# 3_cyber60-1_mcu.net
KiCad netlist of a schematic drawn in Altium Designer
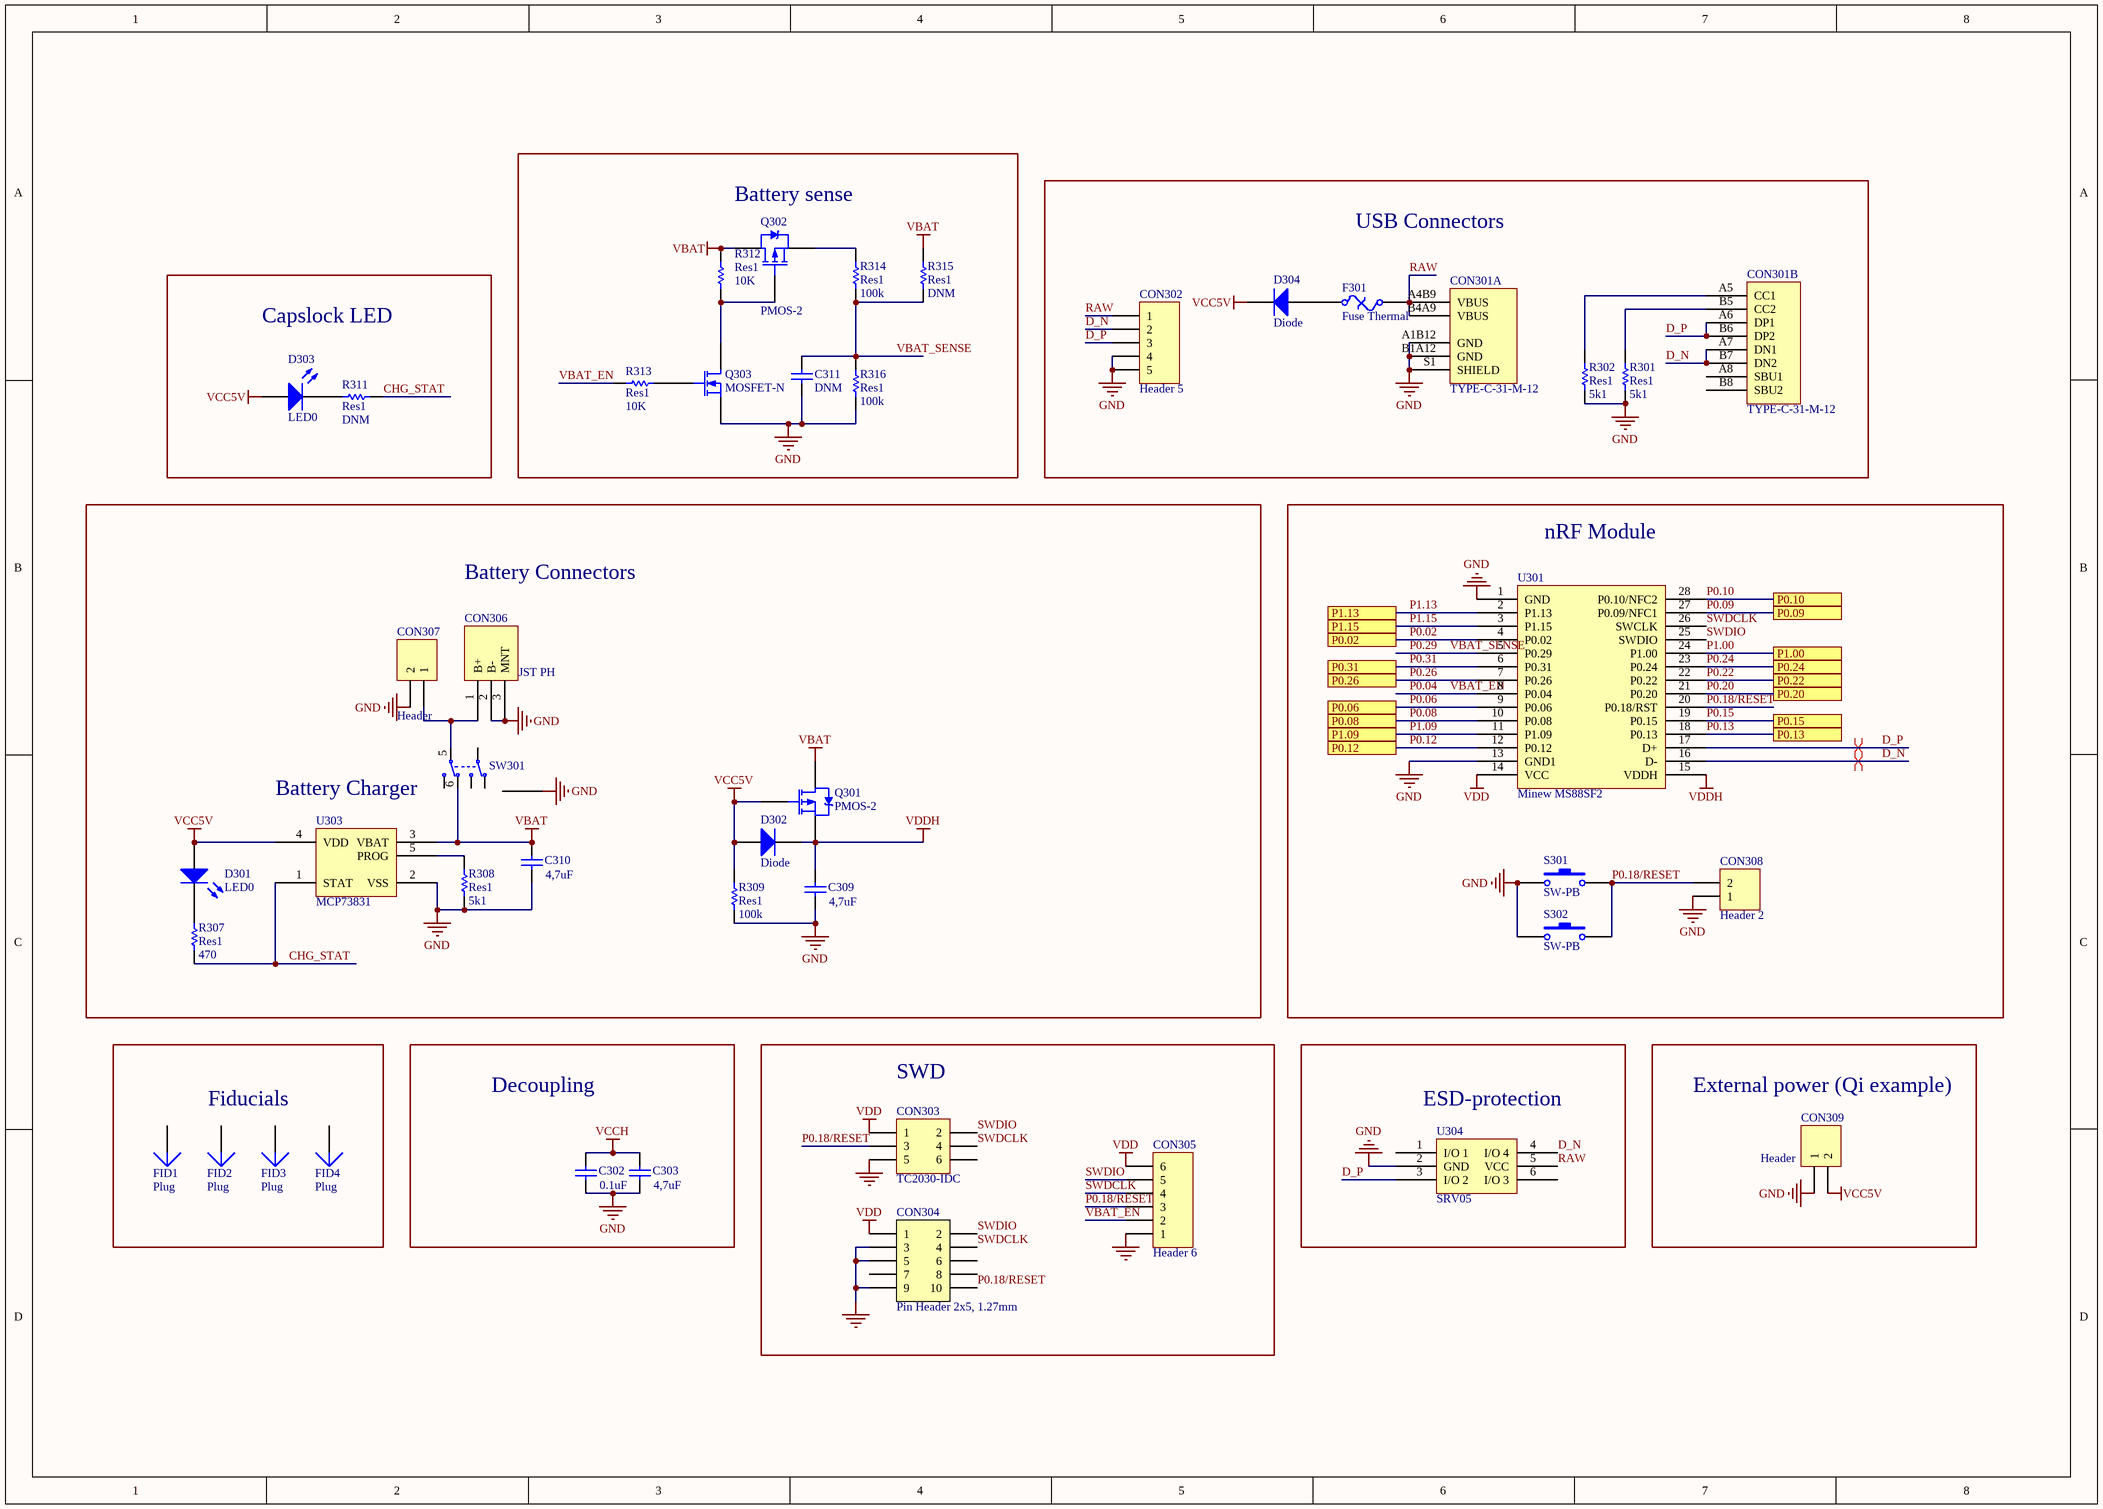
[diagram p0: 3_cyber60-1_mcu.SchDoc]

(export (version "E")
  (design (tool "Eeschema 10.0.6"))
  (components
    (comp (ref "C302")
      (value "0.1uF")
      (footprint "C0603[1608]")
      (description "Capacitor")
      (fields (field (name "MFG") "KEMET") (field (name "LCSC PART #") "C14663"))
      (libsource (lib "Miscellaneous Devices") (part "Cap"))
    )
    (comp (ref "C303")
      (value "4,7uF")
      (footprint "C0603[1608]")
      (description "Capacitor")
      (fields (field (name "LCSC PART #") "C19666") (field (name "MRF.PART") "CL10A475KO8NNNC"))
      (libsource (lib "Miscellaneous Devices") (part "Cap"))
    )
    (comp (ref "C309")
      (value "4,7uF")
      (footprint "C0603[1608]")
      (description "Capacitor")
      (fields (field (name "LCSC PART #") "C19666") (field (name "MRF.PART") "CL10A475KO8NNNC"))
      (libsource (lib "Miscellaneous Devices") (part "Cap"))
    )
    (comp (ref "C310")
      (value "4,7uF")
      (footprint "C0603[1608]")
      (description "Capacitor")
      (fields (field (name "LCSC PART #") "C19666") (field (name "MRF.PART") "CL10A475KO8NNNC"))
      (libsource (lib "Miscellaneous Devices") (part "Cap"))
    )
    (comp (ref "C311")
      (value "DNM")
      (footprint "C0603[1608]")
      (description "Capacitor")
      (libsource (lib "Miscellaneous Devices") (part "Cap"))
    )
    (comp (ref "CON301")
      (value "TYPE-C-31-M-12")
      (footprint "TYPE-C-31-M-12")
      (fields (field (name "MFG") "Korean Hroparts Elec"))
      (libsource (lib "Keebs") (part "TYPE-C-31-M-12"))
    )
    (comp (ref "CON302")
      (value "Header 5")
      (footprint "JST SM04B-SRSS-TB")
      (description "Header, 5-Pin")
      (fields (field (name "MFG") "JST Sales America Inc.") (field (name "MRF.PART") "SM04B-SRSS-TB(LF)(SN)"))
      (libsource (lib "Miscellaneous Connectors") (part "Header 5"))
    )
    (comp (ref "CON303")
      (value "TC2030-IDC")
      (footprint "TC2030-IDC-NL")
      (description "Header, 3-Pin, Dual row")
      (libsource (lib "Miscellaneous Connectors") (part "Header 3X2"))
    )
    (comp (ref "CON304")
      (value "Pin Header 2x5, 1.27mm")
      (footprint "HDR_2x5-SMD-1.27mm-K")
      (description "Pin Header 2x5, 1.27mm (50mil), SMD, Keying Shroud")
      (fields (field (name "MFG") "Samtec Inc."))
      (libsource (lib "Nordic Passive DB") (part "CONN-2x5"))
    )
    (comp (ref "CON305")
      (value "Header 6")
      (footprint "HDR1X6")
      (description "Header, 6-Pin")
      (fields (field (name "PUBLISHER") "Altium Limited"))
      (libsource (lib "Miscellaneous Connectors") (part "Header 6"))
    )
    (comp (ref "CON306")
      (value "JST PH")
      (footprint "JST SM02B-SRSS-TB")
      (fields (field (name "LCSC PART #") "C160402") (field (name "MRF.PART") "SM02B-SRSS-TB(LF)(SN)"))
      (libsource (lib "Keebs") (part "JST S2B-PH-SM4-TB"))
    )
    (comp (ref "CON307")
      (value "Header")
      (footprint "Keebs:JST S2B-PH-K(LF)(SN)")
      (description "Header, 2-Pin")
      (fields (field (name "LCSC PART #") "C265016") (field (name "MRF.PART") "S2B-PH-K(LF)(SN)"))
      (libsource (lib "") (part "Header 2_1"))
    )
    (comp (ref "CON308")
      (value "Header 2")
      (footprint "HDR1X2")
      (description "Header, 2-Pin")
      (libsource (lib "Miscellaneous Connectors") (part "Header 2"))
    )
    (comp (ref "CON309")
      (value "Header")
      (footprint "HDR1X2")
      (description "Header, 2-Pin")
      (libsource (lib "Miscellaneous Connectors") (part "Header 2"))
    )
    (comp (ref "D301")
      (value "LED0")
      (footprint "LED0603[1608]")
      (description "Typical INFRARED GaAs LED")
      (fields (field (name "LCSC PART #") "C72038") (field (name "MRF.PART") "19-213/Y2C-CQ2R2L/3T(CY)"))
      (libsource (lib "Miscellaneous Devices") (part "LED0"))
    )
    (comp (ref "D302")
      (value "Diode")
      (footprint "SOD-123")
      (description "Default Diode")
      (fields (field (name "LCSC PART #") "C8598") (field (name "MRF.PART") "B5819W"))
      (libsource (lib "Miscellaneous Devices") (part "Diode"))
    )
    (comp (ref "D303")
      (value "LED0")
      (footprint "MX-switch - CAPS - LED NO SWITCH")
      (description "Typical INFRARED GaAs LED")
      (fields (field (name "MFG") "Kingbright"))
      (libsource (lib "Miscellaneous Devices") (part "LED0"))
    )
    (comp (ref "D304")
      (value "Diode")
      (footprint "SOD-123")
      (description "Default Diode")
      (fields (field (name "LCSC PART #") "C8598") (field (name "MRF.PART") "B5819W"))
      (libsource (lib "Miscellaneous Devices") (part "Diode"))
    )
    (comp (ref "F301")
      (value "Fuse Thermal")
      (footprint "C1206[3216]")
      (description "Thermal Fuse")
      (fields (field (name "MFG") "Bel Fuse Inc.") (field (name "LCSC PART #") "C135338"))
      (libsource (lib "Miscellaneous Devices") (part "Fuse Thermal"))
    )
    (comp (ref "FID1")
      (value "Plug")
      (footprint "Fiducial_Nordic")
      (libsource (lib "Miscellaneous Connectors") (part "Plug"))
    )
    (comp (ref "FID2")
      (value "Plug")
      (footprint "Fiducial_Nordic")
      (libsource (lib "Miscellaneous Connectors") (part "Plug"))
    )
    (comp (ref "FID3")
      (value "Plug")
      (footprint "Fiducial_Nordic")
      (libsource (lib "Miscellaneous Connectors") (part "Plug"))
    )
    (comp (ref "FID4")
      (value "Plug")
      (footprint "Fiducial_Nordic")
      (libsource (lib "Miscellaneous Connectors") (part "Plug"))
    )
    (comp (ref "Q301")
      (value "PMOS-2")
      (footprint "SOT-23-3")
      (description "P-Channel Power MOSFET")
      (fields (field (name "MRF.PART") "SI2301CDS-T1-GE3") (field (name "LCSC PART #") "C10487"))
      (libsource (lib "Miscellaneous Devices") (part "PMOS-2"))
    )
    (comp (ref "Q302")
      (value "PMOS-2")
      (footprint "SOT-23-3")
      (description "P-Channel Power MOSFET")
      (fields (field (name "MRF.PART") "SI2301CDS-T1-GE3") (field (name "LCSC PART #") "C10487"))
      (libsource (lib "Miscellaneous Devices") (part "PMOS-2"))
    )
    (comp (ref "Q303")
      (value "MOSFET-N")
      (footprint "SOT-23-3")
      (description "N-Channel MOSFET")
      (fields (field (name "LCSC PART #") "C8545") (field (name "MRF.PART") "2N7002"))
      (libsource (lib "Miscellaneous Devices") (part "MOSFET-N"))
    )
    (comp (ref "R301")
      (value "Res1")
      (footprint "R0603[1608]")
      (description "Resistor")
      (fields
        (field (name "ALTIUM_VALUE") "5k1")
        (field (name "MFG") "Panasonic Electronic Components")
        (field (name "LCSC PART #") "C23186")
      )
      (libsource (lib "Miscellaneous Devices") (part "Res1"))
    )
    (comp (ref "R302")
      (value "Res1")
      (footprint "R0603[1608]")
      (description "Resistor")
      (fields
        (field (name "ALTIUM_VALUE") "5k1")
        (field (name "MFG") "Panasonic Electronic Components")
        (field (name "LCSC PART #") "C23186")
      )
      (libsource (lib "Miscellaneous Devices") (part "Res1"))
    )
    (comp (ref "R307")
      (value "Res1")
      (footprint "R0603[1608]")
      (description "Resistor")
      (fields
        (field (name "ALTIUM_VALUE") "470")
        (field (name "MFG") "Panasonic Electronic Components")
        (field (name "LCSC PART #") "C23179")
      )
      (libsource (lib "Miscellaneous Devices") (part "Res1"))
    )
    (comp (ref "R308")
      (value "Res1")
      (footprint "R0603[1608]")
      (description "Resistor")
      (fields
        (field (name "ALTIUM_VALUE") "5k1")
        (field (name "MFG") "Panasonic Electronic Components")
        (field (name "LCSC PART #") "C23186")
      )
      (libsource (lib "Miscellaneous Devices") (part "Res1"))
    )
    (comp (ref "R309")
      (value "Res1")
      (footprint "R0603[1608]")
      (description "Resistor")
      (fields
        (field (name "ALTIUM_VALUE") "100k")
        (field (name "MRF.PART") "0603WAF1003T5E")
        (field (name "LCSC PART #") "C25803")
      )
      (libsource (lib "Miscellaneous Devices") (part "Res1"))
    )
    (comp (ref "R311")
      (value "Res1")
      (footprint "R0603[1608]")
      (description "Resistor")
      (fields (field (name "ALTIUM_VALUE") "DNM"))
      (libsource (lib "Miscellaneous Devices") (part "Res1"))
    )
    (comp (ref "R312")
      (value "Res1")
      (footprint "R0603[1608]")
      (description "Resistor")
      (fields
        (field (name "ALTIUM_VALUE") "10K")
        (field (name "MFG") "Panasonic Electronic Components")
        (field (name "LCSC PART #") "C25804")
      )
      (libsource (lib "Miscellaneous Devices") (part "Res1"))
    )
    (comp (ref "R313")
      (value "Res1")
      (footprint "R0603[1608]")
      (description "Resistor")
      (fields
        (field (name "ALTIUM_VALUE") "10K")
        (field (name "MFG") "Panasonic Electronic Components")
        (field (name "LCSC PART #") "C25804")
      )
      (libsource (lib "Miscellaneous Devices") (part "Res1"))
    )
    (comp (ref "R314")
      (value "Res1")
      (footprint "R0603[1608]")
      (description "Resistor")
      (fields
        (field (name "ALTIUM_VALUE") "100k")
        (field (name "MRF.PART") "0603WAF1003T5E")
        (field (name "LCSC PART #") "C25803")
      )
      (libsource (lib "Miscellaneous Devices") (part "Res1"))
    )
    (comp (ref "R315")
      (value "Res1")
      (footprint "R0603[1608]")
      (description "Resistor")
      (fields (field (name "ALTIUM_VALUE") "DNM") (field (name "MFG") "TE Connectivity Passive Product"))
      (libsource (lib "Miscellaneous Devices") (part "Res1"))
    )
    (comp (ref "R316")
      (value "Res1")
      (footprint "R0603[1608]")
      (description "Resistor")
      (fields
        (field (name "ALTIUM_VALUE") "100k")
        (field (name "MRF.PART") "0603WAF1003T5E")
        (field (name "LCSC PART #") "C25803")
      )
      (libsource (lib "Miscellaneous Devices") (part "Res1"))
    )
    (comp (ref "S301")
      (value "SW-PB")
      (footprint "Combo switch")
      (description "Switch")
      (fields (field (name "MFG") "C&K") (field (name "MRF.PART") "TS-1187A-C-D-B"))
      (libsource (lib "Miscellaneous Devices") (part "SW-PB"))
    )
    (comp (ref "S302")
      (value "SW-PB")
      (footprint "Combo switch")
      (description "Switch")
      (fields (field (name "MFG") "C&K") (field (name "MRF.PART") "TS-1187A-C-D-B"))
      (libsource (lib "Miscellaneous Devices") (part "SW-PB"))
    )
    (comp (ref "SW301")
      (value "~")
      (footprint "AlpsAlpine SSSS820201")
      (description "Slide Switch DPDT")
      (fields (field (name "MRF.PART") "SSSS820201") (field (name "LCSC PART #") "C160879"))
      (libsource (lib "Keebs") (part "MKH-22D14-G2-B"))
    )
    (comp (ref "U301")
      (value "Minew MS88SF2")
      (footprint "Minew MS88SF2")
      (fields (field (name "MFG") "Minew"))
      (libsource (lib "Keebs") (part "Minew MS88SF2"))
    )
    (comp (ref "U303")
      (value "MCP73831")
      (footprint "SOT-23-5")
      (fields (field (name "LCSC PART #") "C32574") (field (name "MRF.PART") "TP4054"))
      (libsource (lib "Keebs") (part "MCP73831"))
    )
    (comp (ref "U304")
      (value "SRV05")
      (footprint "SOT-23-6")
      (fields (field (name "LCSC PART #") "C85364") (field (name "MRF.PART") "SRV05-4-P-T7"))
      (libsource (lib "Keebs") (part "SRV05"))
    )
  )
  (nets
    (net (code "1") (name "/CHG_STAT") (class "Default")
      (node (ref "R307") (pin "1") (pinfunction "1_1") (pintype "passive"))
      (node (ref "R311") (pin "1") (pinfunction "1_1") (pintype "passive"))
      (node (ref "U303") (pin "1") (pinfunction "STAT_1") (pintype "passive"))
    )
    (net (code "2") (name "/D_N") (class "Default")
      (node (ref "CON301") (pin "A7") (pinfunction "DN1_A7") (pintype "passive"))
      (node (ref "CON301") (pin "B7") (pinfunction "DN2_B7") (pintype "passive"))
      (node (ref "CON302") (pin "2") (pinfunction "2_2") (pintype "passive"))
      (node (ref "U301") (pin "16") (pinfunction "D-_16") (pintype "passive"))
      (node (ref "U304") (pin "4") (pinfunction "I/O_4_4") (pintype "passive"))
    )
    (net (code "3") (name "/D_P") (class "Default")
      (node (ref "CON301") (pin "A6") (pinfunction "DP1_A6") (pintype "passive"))
      (node (ref "CON301") (pin "B6") (pinfunction "DP2_B6") (pintype "passive"))
      (node (ref "CON302") (pin "3") (pinfunction "3_3") (pintype "passive"))
      (node (ref "U301") (pin "17") (pinfunction "D+_17") (pintype "passive"))
      (node (ref "U304") (pin "3") (pinfunction "I/O_2_3") (pintype "passive"))
    )
    (net (code "4") (name "/P0.02") (class "Default")
      (node (ref "U301") (pin "4") (pinfunction "P0.02_4") (pintype "passive"))
    )
    (net (code "5") (name "/P0.04") (class "Default")
      (node (ref "CON305") (pin "2") (pinfunction "2_2") (pintype "passive"))
      (node (ref "R313") (pin "1") (pinfunction "1_1") (pintype "passive"))
      (node (ref "U301") (pin "8") (pinfunction "P0.04_8") (pintype "passive"))
    )
    (net (code "6") (name "/P0.06") (class "Default")
      (node (ref "U301") (pin "9") (pinfunction "P0.06_9") (pintype "passive"))
    )
    (net (code "7") (name "/P0.08") (class "Default")
      (node (ref "U301") (pin "10") (pinfunction "P0.08_10") (pintype "passive"))
    )
    (net (code "8") (name "/P0.09") (class "Default")
      (node (ref "U301") (pin "27") (pinfunction "P0.09/NFC1_27") (pintype "passive"))
    )
    (net (code "9") (name "/P0.10") (class "Default")
      (node (ref "U301") (pin "28") (pinfunction "P0.10/NFC2_28") (pintype "passive"))
    )
    (net (code "10") (name "/P0.12") (class "Default")
      (node (ref "U301") (pin "12") (pinfunction "P0.12_12") (pintype "passive"))
    )
    (net (code "11") (name "/P0.13") (class "Default")
      (node (ref "U301") (pin "18") (pinfunction "P0.13_18") (pintype "passive"))
    )
    (net (code "12") (name "/P0.15") (class "Default")
      (node (ref "U301") (pin "19") (pinfunction "P0.15_19") (pintype "passive"))
    )
    (net (code "13") (name "/P0.18{slash}RESET") (class "Default")
      (node (ref "CON303") (pin "3") (pinfunction "3_3") (pintype "passive"))
      (node (ref "CON304") (pin "10") (pinfunction "10_10") (pintype "passive"))
      (node (ref "CON305") (pin "3") (pinfunction "3_3") (pintype "passive"))
      (node (ref "CON308") (pin "2") (pinfunction "2_2") (pintype "passive"))
      (node (ref "S301") (pin "2") (pinfunction "2_2") (pintype "passive"))
      (node (ref "S302") (pin "1") (pinfunction "1_1") (pintype "passive"))
      (node (ref "U301") (pin "20") (pinfunction "P0.18/RST_20") (pintype "passive"))
    )
    (net (code "14") (name "/P0.20") (class "Default")
      (node (ref "U301") (pin "21") (pinfunction "P0.20_21") (pintype "passive"))
    )
    (net (code "15") (name "/P0.22") (class "Default")
      (node (ref "U301") (pin "22") (pinfunction "P0.22_22") (pintype "passive"))
    )
    (net (code "16") (name "/P0.24") (class "Default")
      (node (ref "U301") (pin "23") (pinfunction "P0.24_23") (pintype "passive"))
    )
    (net (code "17") (name "/P0.26") (class "Default")
      (node (ref "U301") (pin "7") (pinfunction "P0.26_7") (pintype "passive"))
    )
    (net (code "18") (name "/P0.29") (class "Default")
      (node (ref "C311") (pin "2") (pinfunction "2_2") (pintype "passive"))
      (node (ref "R314") (pin "2") (pinfunction "2_2") (pintype "passive"))
      (node (ref "R315") (pin "1") (pinfunction "1_1") (pintype "passive"))
      (node (ref "R316") (pin "1") (pinfunction "1_1") (pintype "passive"))
      (node (ref "U301") (pin "5") (pinfunction "P0.29_5") (pintype "passive"))
    )
    (net (code "19") (name "/P0.31") (class "Default")
      (node (ref "U301") (pin "6") (pinfunction "P0.31_6") (pintype "passive"))
    )
    (net (code "20") (name "/P1.00") (class "Default")
      (node (ref "U301") (pin "24") (pinfunction "P1.00_24") (pintype "passive"))
    )
    (net (code "21") (name "/P1.09") (class "Default")
      (node (ref "U301") (pin "11") (pinfunction "P1.09_11") (pintype "passive"))
    )
    (net (code "22") (name "/P1.13") (class "Default")
      (node (ref "U301") (pin "2") (pinfunction "P1.13_2") (pintype "passive"))
    )
    (net (code "23") (name "/P1.15") (class "Default")
      (node (ref "U301") (pin "3") (pinfunction "P1.15_3") (pintype "passive"))
    )
    (net (code "24") (name "/RAW") (class "Default")
      (node (ref "CON301") (pin "A4B9") (pinfunction "VBUS_A4B9") (pintype "passive"))
      (node (ref "CON301") (pin "B4A9") (pinfunction "VBUS_B4A9") (pintype "passive"))
      (node (ref "CON302") (pin "1") (pinfunction "1_1") (pintype "passive"))
      (node (ref "F301") (pin "2") (pinfunction "2_2") (pintype "passive"))
      (node (ref "U304") (pin "5") (pinfunction "VCC_5") (pintype "passive"))
    )
    (net (code "25") (name "/SWDCLK") (class "Default")
      (node (ref "CON303") (pin "4") (pinfunction "4_4") (pintype "passive"))
      (node (ref "CON304") (pin "4") (pinfunction "4_4") (pintype "passive"))
      (node (ref "CON305") (pin "4") (pinfunction "4_4") (pintype "passive"))
      (node (ref "U301") (pin "26") (pinfunction "SWCLK_26") (pintype "passive"))
    )
    (net (code "26") (name "/SWDIO") (class "Default")
      (node (ref "CON303") (pin "2") (pinfunction "2_2") (pintype "passive"))
      (node (ref "CON304") (pin "2") (pinfunction "2_2") (pintype "passive"))
      (node (ref "CON305") (pin "5") (pinfunction "5_5") (pintype "passive"))
      (node (ref "U301") (pin "25") (pinfunction "SWDIO_25") (pintype "passive"))
    )
    (net (code "27") (name "GND") (class "Default")
      (node (ref "C302") (pin "1") (pinfunction "1_1") (pintype "passive"))
      (node (ref "C303") (pin "1") (pinfunction "1_1") (pintype "passive"))
      (node (ref "C309") (pin "1") (pinfunction "1_1") (pintype "passive"))
      (node (ref "C310") (pin "1") (pinfunction "1_1") (pintype "passive"))
      (node (ref "C311") (pin "1") (pinfunction "1_1") (pintype "passive"))
      (node (ref "CON301") (pin "A1B12") (pinfunction "GND_A1B12") (pintype "passive"))
      (node (ref "CON301") (pin "B1A12") (pinfunction "GND_B1A12") (pintype "passive"))
      (node (ref "CON301") (pin "S1") (pinfunction "SHIELD_S1") (pintype "passive"))
      (node (ref "CON302") (pin "4") (pinfunction "4_4") (pintype "passive"))
      (node (ref "CON302") (pin "5") (pinfunction "5_5") (pintype "passive"))
      (node (ref "CON303") (pin "5") (pinfunction "5_5") (pintype "passive"))
      (node (ref "CON304") (pin "3") (pinfunction "3_3") (pintype "passive"))
      (node (ref "CON304") (pin "5") (pinfunction "5_5") (pintype "passive"))
      (node (ref "CON304") (pin "9") (pinfunction "9_9") (pintype "passive"))
      (node (ref "CON305") (pin "1") (pinfunction "1_1") (pintype "passive"))
      (node (ref "CON306") (pin "2") (pinfunction "B-_2") (pintype "passive"))
      (node (ref "CON306") (pin "3") (pinfunction "MNT_3") (pintype "passive"))
      (node (ref "CON307") (pin "2") (pinfunction "2_2") (pintype "passive"))
      (node (ref "CON308") (pin "1") (pinfunction "1_1") (pintype "passive"))
      (node (ref "CON309") (pin "1") (pinfunction "1_1") (pintype "passive"))
      (node (ref "Q303") (pin "2") (pinfunction "S_2") (pintype "passive"))
      (node (ref "R301") (pin "2") (pinfunction "2_2") (pintype "passive"))
      (node (ref "R302") (pin "2") (pinfunction "2_2") (pintype "passive"))
      (node (ref "R308") (pin "2") (pinfunction "2_2") (pintype "passive"))
      (node (ref "R309") (pin "2") (pinfunction "2_2") (pintype "passive"))
      (node (ref "R316") (pin "2") (pinfunction "2_2") (pintype "passive"))
      (node (ref "S301") (pin "1") (pinfunction "1_1") (pintype "passive"))
      (node (ref "S302") (pin "2") (pinfunction "2_2") (pintype "passive"))
      (node (ref "SW301") (pin "7") (pinfunction "MNT_7") (pintype "passive"))
      (node (ref "U301") (pin "1") (pinfunction "GND_1") (pintype "passive"))
      (node (ref "U301") (pin "13") (pinfunction "GND1_13") (pintype "passive"))
      (node (ref "U303") (pin "2") (pinfunction "VSS_2") (pintype "passive"))
      (node (ref "U304") (pin "2") (pinfunction "GND_2") (pintype "passive"))
    )
    (net (code "28") (name "Net-(CON301B-CC1)") (class "Default")
      (node (ref "CON301") (pin "A5") (pinfunction "CC1_A5") (pintype "passive"))
      (node (ref "R302") (pin "1") (pinfunction "1_1") (pintype "passive"))
    )
    (net (code "29") (name "Net-(CON301B-CC2)") (class "Default")
      (node (ref "CON301") (pin "B5") (pinfunction "CC2_B5") (pintype "passive"))
      (node (ref "R301") (pin "1") (pinfunction "1_1") (pintype "passive"))
    )
    (net (code "30") (name "Net-(CON306-B+)") (class "Default")
      (node (ref "CON306") (pin "1") (pinfunction "B+_1") (pintype "passive"))
      (node (ref "CON307") (pin "1") (pinfunction "1_1") (pintype "passive"))
      (node (ref "SW301") (pin "5") (pinfunction "COM-2_5") (pintype "passive"))
    )
    (net (code "31") (name "Net-(D301-K)") (class "Default")
      (node (ref "D301") (pin "2") (pinfunction "K_2") (pintype "passive"))
      (node (ref "R307") (pin "2") (pinfunction "2_2") (pintype "passive"))
    )
    (net (code "32") (name "Net-(D303-K)") (class "Default")
      (node (ref "D303") (pin "2") (pinfunction "K_2") (pintype "passive"))
      (node (ref "R311") (pin "2") (pinfunction "2_2") (pintype "passive"))
    )
    (net (code "33") (name "Net-(D304-A)") (class "Default")
      (node (ref "D304") (pin "1") (pinfunction "A_1") (pintype "passive"))
      (node (ref "F301") (pin "1") (pinfunction "1_1") (pintype "passive"))
    )
    (net (code "34") (name "Net-(Q302-G)") (class "Default")
      (node (ref "Q302") (pin "1") (pinfunction "G_1") (pintype "passive"))
      (node (ref "Q303") (pin "3") (pinfunction "D_3") (pintype "passive"))
      (node (ref "R312") (pin "2") (pinfunction "2_2") (pintype "passive"))
    )
    (net (code "35") (name "Net-(Q302-S)") (class "Default")
      (node (ref "Q302") (pin "2") (pinfunction "S_2") (pintype "passive"))
      (node (ref "R314") (pin "1") (pinfunction "1_1") (pintype "passive"))
    )
    (net (code "36") (name "Net-(Q303-G)") (class "Default")
      (node (ref "Q303") (pin "1") (pinfunction "G_1") (pintype "passive"))
      (node (ref "R313") (pin "2") (pinfunction "2_2") (pintype "passive"))
    )
    (net (code "37") (name "Net-(U303-PROG)") (class "Default")
      (node (ref "R308") (pin "1") (pinfunction "1_1") (pintype "passive"))
      (node (ref "U303") (pin "5") (pinfunction "PROG_5") (pintype "passive"))
    )
    (net (code "38") (name "VBAT") (class "Default")
      (node (ref "C310") (pin "2") (pinfunction "2_2") (pintype "passive"))
      (node (ref "Q301") (pin "3") (pinfunction "D_3") (pintype "passive"))
      (node (ref "Q302") (pin "3") (pinfunction "D_3") (pintype "passive"))
      (node (ref "R312") (pin "1") (pinfunction "1_1") (pintype "passive"))
      (node (ref "R315") (pin "2") (pinfunction "2_2") (pintype "passive"))
      (node (ref "SW301") (pin "6") (pinfunction "N.C-2_6") (pintype "passive"))
      (node (ref "U303") (pin "3") (pinfunction "VBAT_3") (pintype "passive"))
    )
    (net (code "39") (name "VCC5V") (class "Default")
      (node (ref "CON309") (pin "2") (pinfunction "2_2") (pintype "passive"))
      (node (ref "D301") (pin "1") (pinfunction "A_1") (pintype "passive"))
      (node (ref "D302") (pin "1") (pinfunction "A_1") (pintype "passive"))
      (node (ref "D303") (pin "1") (pinfunction "A_1") (pintype "passive"))
      (node (ref "D304") (pin "2") (pinfunction "K_2") (pintype "passive"))
      (node (ref "Q301") (pin "1") (pinfunction "G_1") (pintype "passive"))
      (node (ref "R309") (pin "1") (pinfunction "1_1") (pintype "passive"))
      (node (ref "U303") (pin "4") (pinfunction "VDD_4") (pintype "passive"))
    )
    (net (code "40") (name "VCCH") (class "Default")
      (node (ref "C302") (pin "2") (pinfunction "2_2") (pintype "passive"))
      (node (ref "C303") (pin "2") (pinfunction "2_2") (pintype "passive"))
    )
    (net (code "41") (name "VDD") (class "Default")
      (node (ref "CON303") (pin "1") (pinfunction "1_1") (pintype "passive"))
      (node (ref "CON304") (pin "1") (pinfunction "1_1") (pintype "passive"))
      (node (ref "CON305") (pin "6") (pinfunction "6_6") (pintype "passive"))
      (node (ref "U301") (pin "14") (pinfunction "VCC_14") (pintype "passive"))
    )
    (net (code "42") (name "VDDH") (class "Default")
      (node (ref "C309") (pin "2") (pinfunction "2_2") (pintype "passive"))
      (node (ref "D302") (pin "2") (pinfunction "K_2") (pintype "passive"))
      (node (ref "Q301") (pin "2") (pinfunction "S_2") (pintype "passive"))
      (node (ref "U301") (pin "15") (pinfunction "VDDH_15") (pintype "passive"))
    )
    (net (code "43") (name "unconnected-(CON301B-SBU1-PadA8)") (class "Default")
      (node (ref "CON301") (pin "A8") (pinfunction "SBU1_A8") (pintype "passive"))
    )
    (net (code "44") (name "unconnected-(CON301B-SBU2-PadB8)") (class "Default")
      (node (ref "CON301") (pin "B8") (pinfunction "SBU2_B8") (pintype "passive"))
    )
    (net (code "45") (name "unconnected-(CON303-Pad6)") (class "Default")
      (node (ref "CON303") (pin "6") (pinfunction "6_6") (pintype "passive"))
    )
    (net (code "46") (name "unconnected-(CON304-Pad6)") (class "Default")
      (node (ref "CON304") (pin "6") (pinfunction "6_6") (pintype "passive"))
    )
    (net (code "47") (name "unconnected-(CON304-Pad7)") (class "Default")
      (node (ref "CON304") (pin "7") (pinfunction "7_7") (pintype "passive"))
    )
    (net (code "48") (name "unconnected-(CON304-Pad8)") (class "Default")
      (node (ref "CON304") (pin "8") (pinfunction "8_8") (pintype "passive"))
    )
    (net (code "49") (name "unconnected-(FID1-Pad1)") (class "Default")
      (node (ref "FID1") (pin "1") (pinfunction "1_1") (pintype "passive"))
    )
    (net (code "50") (name "unconnected-(FID2-Pad1)") (class "Default")
      (node (ref "FID2") (pin "1") (pinfunction "1_1") (pintype "passive"))
    )
    (net (code "51") (name "unconnected-(FID3-Pad1)") (class "Default")
      (node (ref "FID3") (pin "1") (pinfunction "1_1") (pintype "passive"))
    )
    (net (code "52") (name "unconnected-(FID4-Pad1)") (class "Default")
      (node (ref "FID4") (pin "1") (pinfunction "1_1") (pintype "passive"))
    )
    (net (code "53") (name "unconnected-(SW301-COM-1-Pad2)") (class "Default")
      (node (ref "SW301") (pin "2") (pinfunction "COM-1_2") (pintype "passive"))
    )
    (net (code "54") (name "unconnected-(SW301-N.C-1-Pad3)") (class "Default")
      (node (ref "SW301") (pin "3") (pinfunction "N.C-1_3") (pintype "passive"))
    )
    (net (code "55") (name "unconnected-(SW301-N.O-1-Pad1)") (class "Default")
      (node (ref "SW301") (pin "1") (pinfunction "N.O-1_1") (pintype "passive"))
    )
    (net (code "56") (name "unconnected-(SW301-N.O-2-Pad4)") (class "Default")
      (node (ref "SW301") (pin "4") (pinfunction "N.O-2_4") (pintype "passive"))
    )
    (net (code "57") (name "unconnected-(U304-I{slash}O_1-Pad1)") (class "Default")
      (node (ref "U304") (pin "1") (pinfunction "I/O_1_1") (pintype "passive"))
    )
    (net (code "58") (name "unconnected-(U304-I{slash}O_3-Pad6)") (class "Default")
      (node (ref "U304") (pin "6") (pinfunction "I/O_3_6") (pintype "passive"))
    )
  )
)
